# USB_hub_FTDI.net
KiCad netlist of a schematic drawn in EAGLE
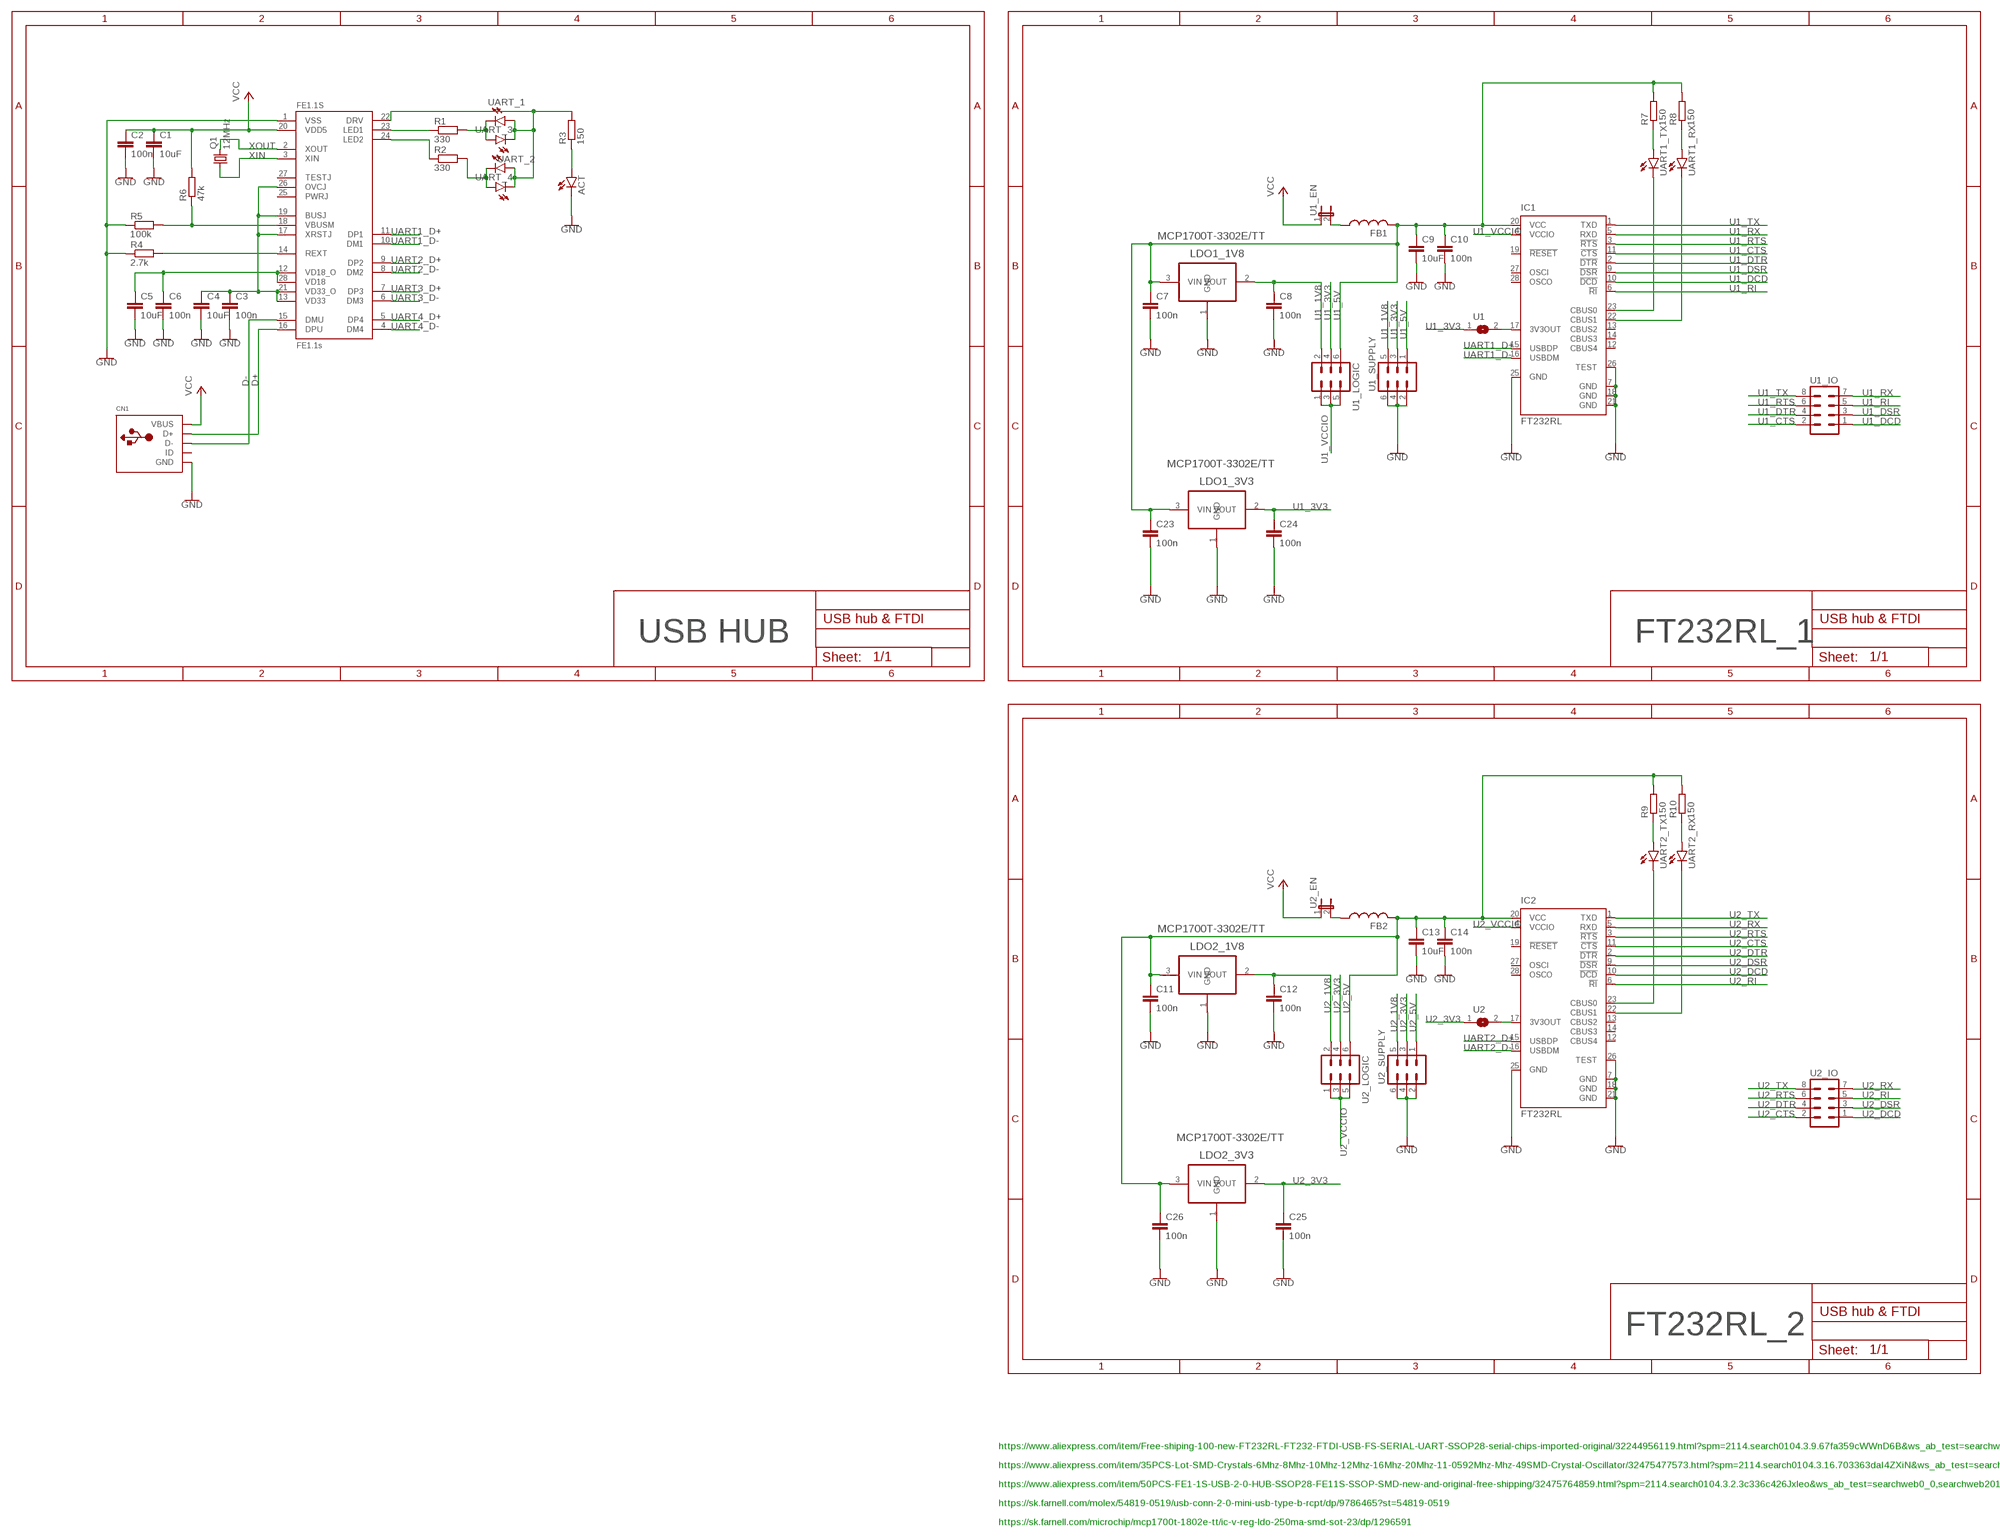
[diagram p0: schematic, sheet 1, part 1 of 2]
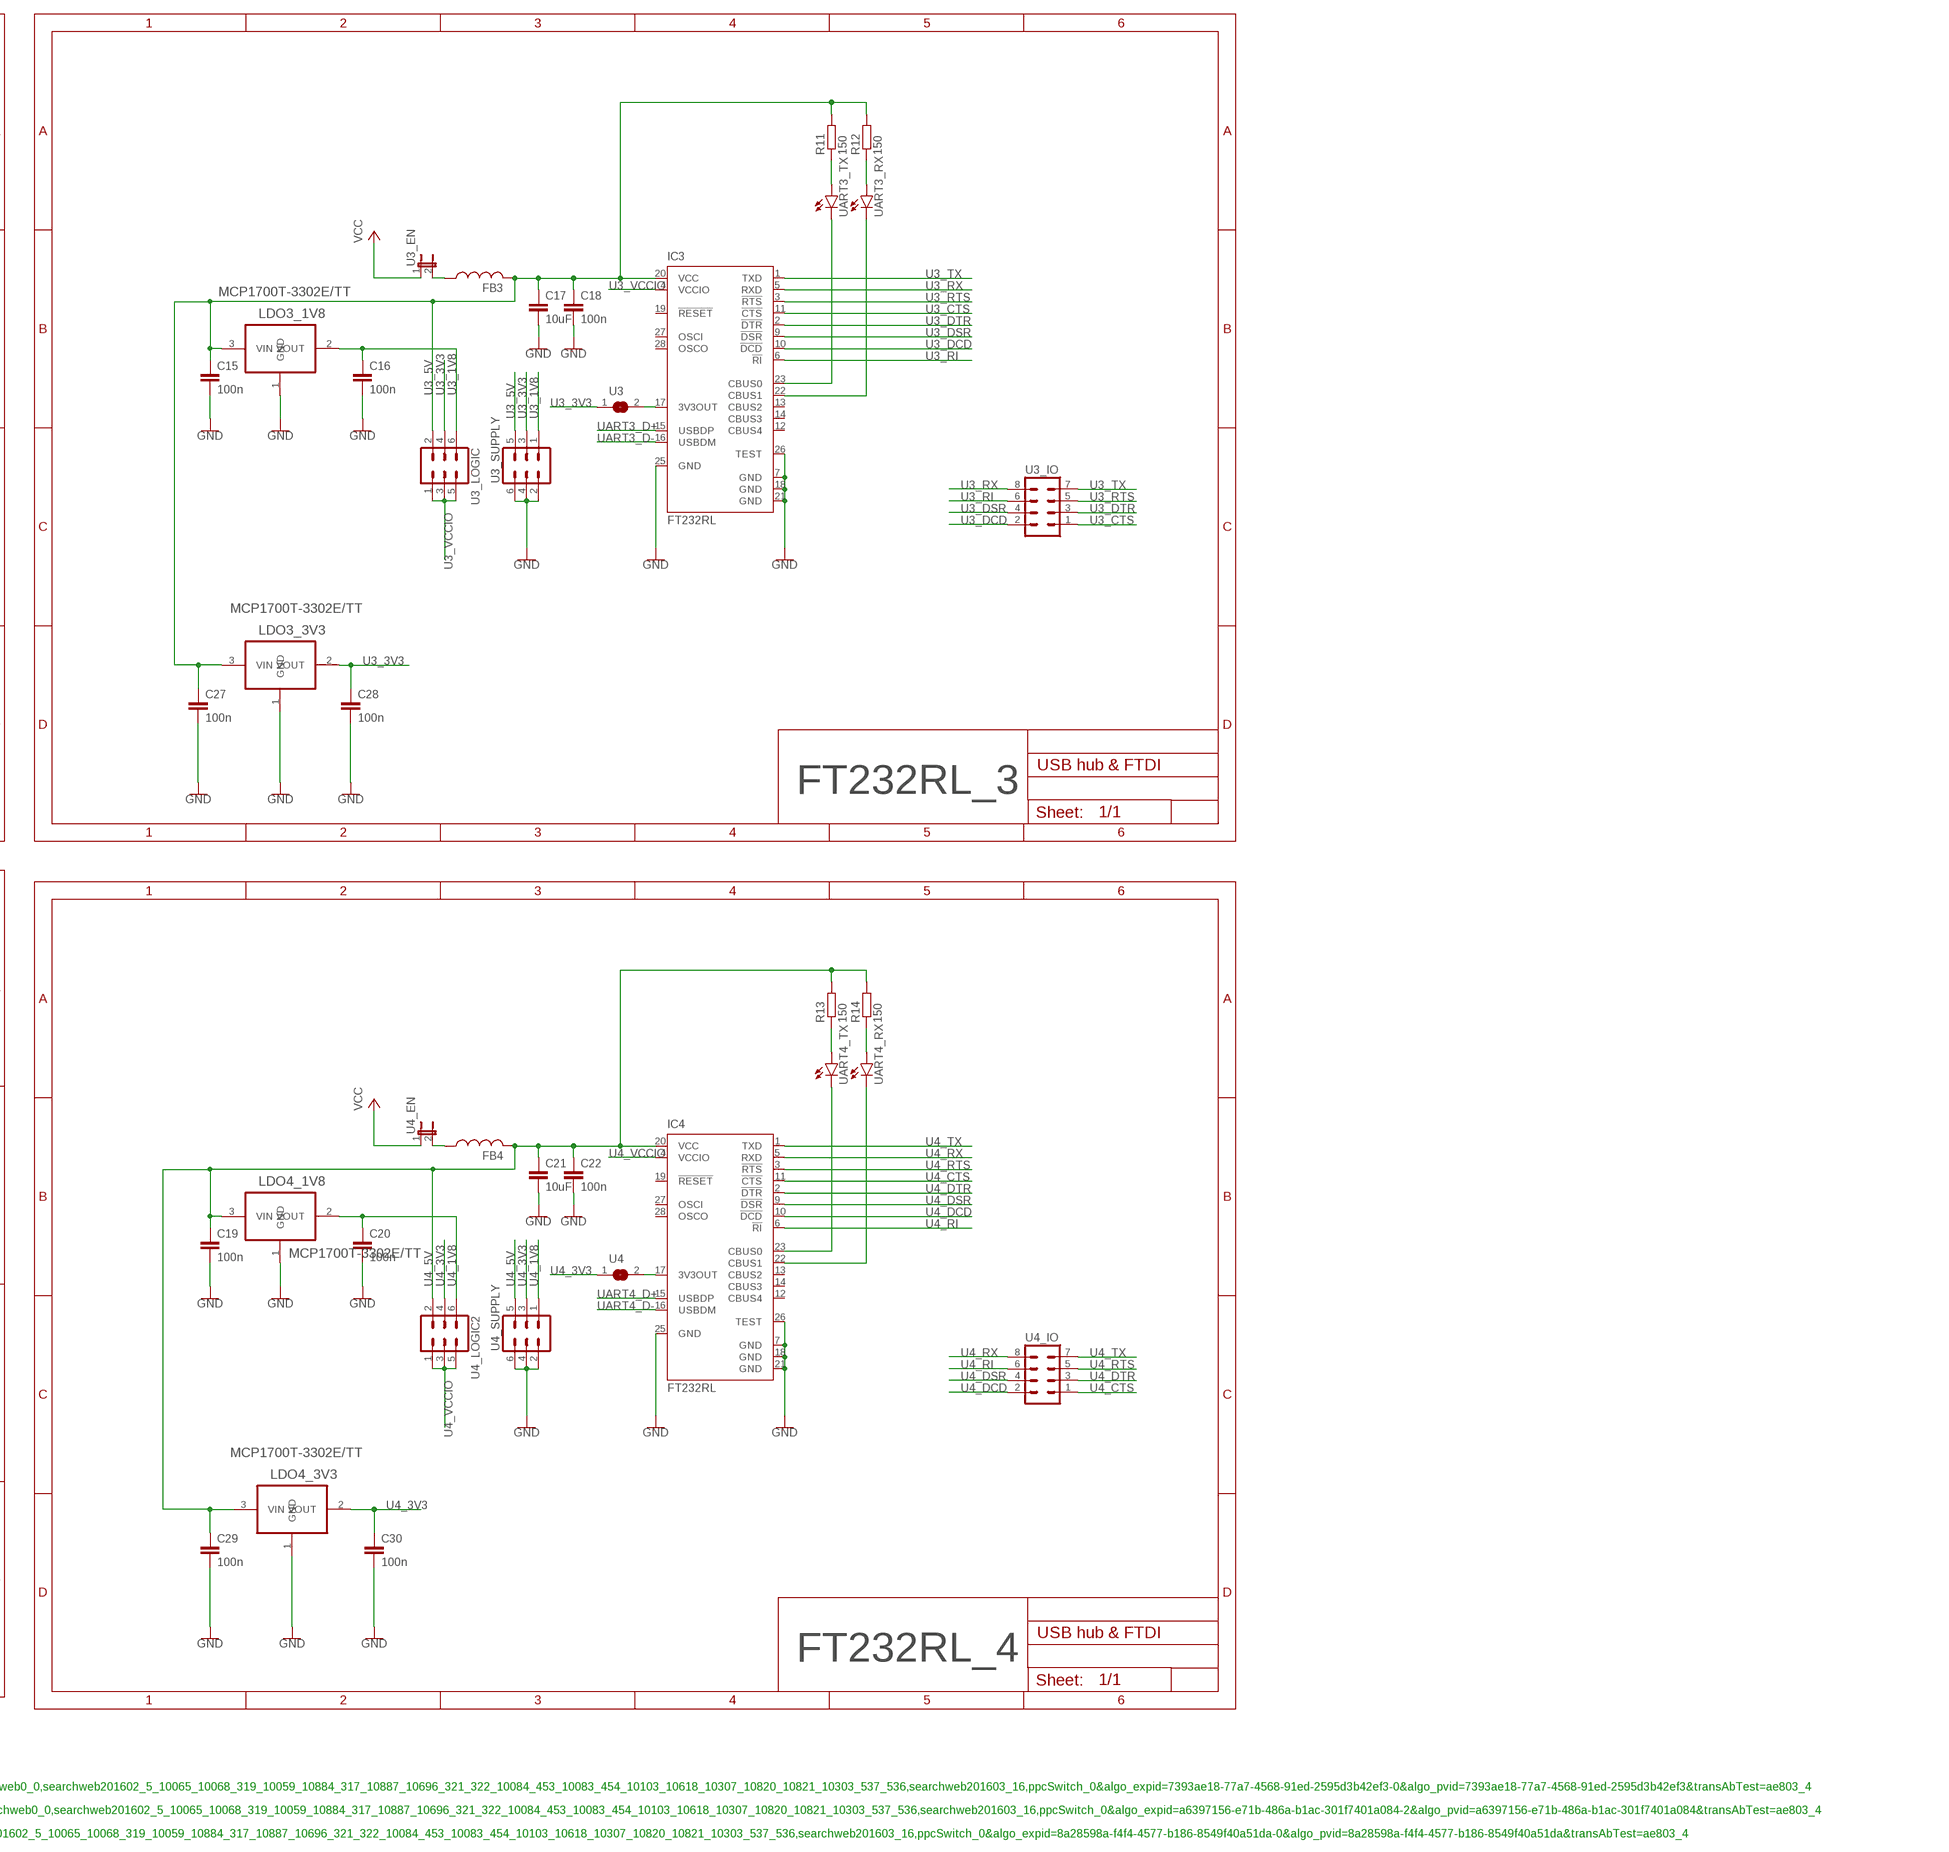
[diagram p1: schematic, sheet 1, part 2 of 2]

(export (version "E")
  (design (tool "Eeschema 10.0.6"))
  (components
    (comp (ref "ACT")
      (value "LEDCHIP-LED0805")
      (footprint "eagle-import:CHIP-LED0805")
      (libsource (lib "eagle-import") (part "LEDCHIP-LED0805"))
    )
    (comp (ref "C1")
      (value "10uF")
      (footprint "eagle-import:C0805")
      (libsource (lib "eagle-import") (part "C-EUC0805"))
    )
    (comp (ref "C2")
      (value "100n")
      (footprint "eagle-import:C0805")
      (libsource (lib "eagle-import") (part "C-EUC0805"))
    )
    (comp (ref "C3")
      (value "100n")
      (footprint "eagle-import:C0805")
      (libsource (lib "eagle-import") (part "C-EUC0805"))
    )
    (comp (ref "C4")
      (value "10uF")
      (footprint "eagle-import:C0805")
      (libsource (lib "eagle-import") (part "C-EUC0805"))
    )
    (comp (ref "C5")
      (value "10uF")
      (footprint "eagle-import:C0805")
      (libsource (lib "eagle-import") (part "C-EUC0805"))
    )
    (comp (ref "C6")
      (value "100n")
      (footprint "eagle-import:C0805")
      (libsource (lib "eagle-import") (part "C-EUC0805"))
    )
    (comp (ref "C7")
      (value "100n")
      (footprint "eagle-import:C0805")
      (libsource (lib "eagle-import") (part "C-EUC0805"))
    )
    (comp (ref "C8")
      (value "100n")
      (footprint "eagle-import:C0805")
      (libsource (lib "eagle-import") (part "C-EUC0805"))
    )
    (comp (ref "C9")
      (value "10uF")
      (footprint "eagle-import:C0805")
      (libsource (lib "eagle-import") (part "C-EUC0805"))
    )
    (comp (ref "C10")
      (value "100n")
      (footprint "eagle-import:C0805")
      (libsource (lib "eagle-import") (part "C-EUC0805"))
    )
    (comp (ref "C11")
      (value "100n")
      (footprint "eagle-import:C0805")
      (libsource (lib "eagle-import") (part "C-EUC0805"))
    )
    (comp (ref "C12")
      (value "100n")
      (footprint "eagle-import:C0805")
      (libsource (lib "eagle-import") (part "C-EUC0805"))
    )
    (comp (ref "C13")
      (value "10uF")
      (footprint "eagle-import:C0805")
      (libsource (lib "eagle-import") (part "C-EUC0805"))
    )
    (comp (ref "C14")
      (value "100n")
      (footprint "eagle-import:C0805")
      (libsource (lib "eagle-import") (part "C-EUC0805"))
    )
    (comp (ref "C15")
      (value "100n")
      (footprint "eagle-import:C0805")
      (libsource (lib "eagle-import") (part "C-EUC0805"))
    )
    (comp (ref "C16")
      (value "100n")
      (footprint "eagle-import:C0805")
      (libsource (lib "eagle-import") (part "C-EUC0805"))
    )
    (comp (ref "C17")
      (value "10uF")
      (footprint "eagle-import:C0805")
      (libsource (lib "eagle-import") (part "C-EUC0805"))
    )
    (comp (ref "C18")
      (value "100n")
      (footprint "eagle-import:C0805")
      (libsource (lib "eagle-import") (part "C-EUC0805"))
    )
    (comp (ref "C19")
      (value "100n")
      (footprint "eagle-import:C0805")
      (libsource (lib "eagle-import") (part "C-EUC0805"))
    )
    (comp (ref "C20")
      (value "100n")
      (footprint "eagle-import:C0805")
      (libsource (lib "eagle-import") (part "C-EUC0805"))
    )
    (comp (ref "C21")
      (value "10uF")
      (footprint "eagle-import:C0805")
      (libsource (lib "eagle-import") (part "C-EUC0805"))
    )
    (comp (ref "C22")
      (value "100n")
      (footprint "eagle-import:C0805")
      (libsource (lib "eagle-import") (part "C-EUC0805"))
    )
    (comp (ref "C23")
      (value "100n")
      (footprint "eagle-import:C0805")
      (libsource (lib "eagle-import") (part "C-EUC0805"))
    )
    (comp (ref "C24")
      (value "100n")
      (footprint "eagle-import:C0805")
      (libsource (lib "eagle-import") (part "C-EUC0805"))
    )
    (comp (ref "C25")
      (value "100n")
      (footprint "eagle-import:C0805")
      (libsource (lib "eagle-import") (part "C-EUC0805"))
    )
    (comp (ref "C26")
      (value "100n")
      (footprint "eagle-import:C0805")
      (libsource (lib "eagle-import") (part "C-EUC0805"))
    )
    (comp (ref "C27")
      (value "100n")
      (footprint "eagle-import:C0805")
      (libsource (lib "eagle-import") (part "C-EUC0805"))
    )
    (comp (ref "C28")
      (value "100n")
      (footprint "eagle-import:C0805")
      (libsource (lib "eagle-import") (part "C-EUC0805"))
    )
    (comp (ref "C29")
      (value "100n")
      (footprint "eagle-import:C0805")
      (libsource (lib "eagle-import") (part "C-EUC0805"))
    )
    (comp (ref "C30")
      (value "100n")
      (footprint "eagle-import:C0805")
      (libsource (lib "eagle-import") (part "C-EUC0805"))
    )
    (comp (ref "CN1")
      (value "USBMOLEX")
      (footprint "eagle-import:USB-MINIB-THM-MOLEX")
      (libsource (lib "eagle-import") (part "USBMOLEX"))
    )
    (comp (ref "FB1")
      (value "FERRITE-BEADB")
      (footprint "eagle-import:0805")
      (libsource (lib "eagle-import") (part "FERRITE-BEADB"))
    )
    (comp (ref "FB2")
      (value "FERRITE-BEADB")
      (footprint "eagle-import:0805")
      (libsource (lib "eagle-import") (part "FERRITE-BEADB"))
    )
    (comp (ref "FB3")
      (value "FERRITE-BEADB")
      (footprint "eagle-import:0805")
      (libsource (lib "eagle-import") (part "FERRITE-BEADB"))
    )
    (comp (ref "FB4")
      (value "FERRITE-BEADB")
      (footprint "eagle-import:0805")
      (libsource (lib "eagle-import") (part "FERRITE-BEADB"))
    )
    (comp (ref "FE1.1S")
      (value "FE1.1S")
      (footprint "eagle-import:FE1.1S_SSOP-28")
      (libsource (lib "eagle-import") (part "FE1.1S"))
    )
    (comp (ref "IC1")
      (value "FT232RL")
      (footprint "eagle-import:SSOP28")
      (libsource (lib "eagle-import") (part "FT232RL"))
    )
    (comp (ref "IC2")
      (value "FT232RL")
      (footprint "eagle-import:SSOP28")
      (libsource (lib "eagle-import") (part "FT232RL"))
    )
    (comp (ref "IC3")
      (value "FT232RL")
      (footprint "eagle-import:SSOP28")
      (libsource (lib "eagle-import") (part "FT232RL"))
    )
    (comp (ref "IC4")
      (value "FT232RL")
      (footprint "eagle-import:SSOP28")
      (libsource (lib "eagle-import") (part "FT232RL"))
    )
    (comp (ref "LDO1_1V8")
      (value "MCP1700T-3302E/TT")
      (footprint "eagle-import:SOT95P237X112-3N")
      (fields (field (name "MF") "Microchip"))
      (libsource (lib "eagle-import") (part "MCP1700T-3302E/TT"))
    )
    (comp (ref "LDO1_3V3")
      (value "MCP1700T-3302E/TT")
      (footprint "eagle-import:SOT95P237X112-3N")
      (fields (field (name "MF") "Microchip"))
      (libsource (lib "eagle-import") (part "MCP1700T-3302E/TT"))
    )
    (comp (ref "LDO2_1V8")
      (value "MCP1700T-3302E/TT")
      (footprint "eagle-import:SOT95P237X112-3N")
      (fields (field (name "MF") "Microchip"))
      (libsource (lib "eagle-import") (part "MCP1700T-3302E/TT"))
    )
    (comp (ref "LDO2_3V3")
      (value "MCP1700T-3302E/TT")
      (footprint "eagle-import:SOT95P237X112-3N")
      (fields (field (name "MF") "Microchip"))
      (libsource (lib "eagle-import") (part "MCP1700T-3302E/TT"))
    )
    (comp (ref "LDO3_1V8")
      (value "MCP1700T-3302E/TT")
      (footprint "eagle-import:SOT95P237X112-3N")
      (fields (field (name "MF") "Microchip"))
      (libsource (lib "eagle-import") (part "MCP1700T-3302E/TT"))
    )
    (comp (ref "LDO3_3V3")
      (value "MCP1700T-3302E/TT")
      (footprint "eagle-import:SOT95P237X112-3N")
      (fields (field (name "MF") "Microchip"))
      (libsource (lib "eagle-import") (part "MCP1700T-3302E/TT"))
    )
    (comp (ref "LDO4_1V8")
      (value "MCP1700T-3302E/TT")
      (footprint "eagle-import:SOT95P237X112-3N")
      (fields (field (name "MF") "Microchip"))
      (libsource (lib "eagle-import") (part "MCP1700T-3302E/TT"))
    )
    (comp (ref "LDO4_3V3")
      (value "MCP1700T-3302E/TT")
      (footprint "eagle-import:SOT95P237X112-3N")
      (fields (field (name "MF") "Microchip"))
      (libsource (lib "eagle-import") (part "MCP1700T-3302E/TT"))
    )
    (comp (ref "Q1")
      (value "12MHz")
      (footprint "eagle-import:HC49UP")
      (libsource (lib "eagle-import") (part "CRYSTALHC49UP"))
    )
    (comp (ref "R1")
      (value "330")
      (footprint "eagle-import:R0805W")
      (libsource (lib "eagle-import") (part "R-EU_R0805W"))
    )
    (comp (ref "R2")
      (value "330")
      (footprint "eagle-import:R0805W")
      (libsource (lib "eagle-import") (part "R-EU_R0805W"))
    )
    (comp (ref "R3")
      (value "150")
      (footprint "eagle-import:R0805W")
      (libsource (lib "eagle-import") (part "R-EU_R0805W"))
    )
    (comp (ref "R4")
      (value "2.7k")
      (footprint "eagle-import:R0805W")
      (libsource (lib "eagle-import") (part "R-EU_R0805W"))
    )
    (comp (ref "R5")
      (value "100k")
      (footprint "eagle-import:R0805W")
      (libsource (lib "eagle-import") (part "R-EU_R0805W"))
    )
    (comp (ref "R6")
      (value "47k")
      (footprint "eagle-import:R0805W")
      (libsource (lib "eagle-import") (part "R-EU_R0805W"))
    )
    (comp (ref "R7")
      (value "150")
      (footprint "eagle-import:R0805W")
      (libsource (lib "eagle-import") (part "R-EU_R0805W"))
    )
    (comp (ref "R8")
      (value "150")
      (footprint "eagle-import:R0805W")
      (libsource (lib "eagle-import") (part "R-EU_R0805W"))
    )
    (comp (ref "R9")
      (value "150")
      (footprint "eagle-import:R0805W")
      (libsource (lib "eagle-import") (part "R-EU_R0805W"))
    )
    (comp (ref "R10")
      (value "150")
      (footprint "eagle-import:R0805W")
      (libsource (lib "eagle-import") (part "R-EU_R0805W"))
    )
    (comp (ref "R11")
      (value "150")
      (footprint "eagle-import:R0805W")
      (libsource (lib "eagle-import") (part "R-EU_R0805W"))
    )
    (comp (ref "R12")
      (value "150")
      (footprint "eagle-import:R0805W")
      (libsource (lib "eagle-import") (part "R-EU_R0805W"))
    )
    (comp (ref "R13")
      (value "150")
      (footprint "eagle-import:R0805W")
      (libsource (lib "eagle-import") (part "R-EU_R0805W"))
    )
    (comp (ref "R14")
      (value "150")
      (footprint "eagle-import:R0805W")
      (libsource (lib "eagle-import") (part "R-EU_R0805W"))
    )
    (comp (ref "U1") (value "SJ") (footprint "eagle-import:SJ") (libsource (lib "eagle-import") (part "SJ")))
    (comp (ref "U1_EN")
      (value "JP1E")
      (footprint "eagle-import:JP1")
      (libsource (lib "eagle-import") (part "JP1E"))
    )
    (comp (ref "U1_IO")
      (value "MA04-2")
      (footprint "eagle-import:MA04-2")
      (libsource (lib "eagle-import") (part "MA04-2"))
    )
    (comp (ref "U1_LOGIC")
      (value "MA03-2")
      (footprint "eagle-import:MA03-2")
      (libsource (lib "eagle-import") (part "MA03-2"))
    )
    (comp (ref "U1_SUPPLY")
      (value "MA03-2")
      (footprint "eagle-import:MA03-2")
      (libsource (lib "eagle-import") (part "MA03-2"))
    )
    (comp (ref "U2") (value "SJ") (footprint "eagle-import:SJ") (libsource (lib "eagle-import") (part "SJ")))
    (comp (ref "U2_EN")
      (value "JP1E")
      (footprint "eagle-import:JP1")
      (libsource (lib "eagle-import") (part "JP1E"))
    )
    (comp (ref "U2_IO")
      (value "MA04-2")
      (footprint "eagle-import:MA04-2")
      (libsource (lib "eagle-import") (part "MA04-2"))
    )
    (comp (ref "U2_LOGIC")
      (value "MA03-2")
      (footprint "eagle-import:MA03-2")
      (libsource (lib "eagle-import") (part "MA03-2"))
    )
    (comp (ref "U2_SUPPLY")
      (value "MA03-2")
      (footprint "eagle-import:MA03-2")
      (libsource (lib "eagle-import") (part "MA03-2"))
    )
    (comp (ref "U3") (value "SJ") (footprint "eagle-import:SJ") (libsource (lib "eagle-import") (part "SJ")))
    (comp (ref "U3_EN")
      (value "JP1E")
      (footprint "eagle-import:JP1")
      (libsource (lib "eagle-import") (part "JP1E"))
    )
    (comp (ref "U3_IO")
      (value "MA04-2")
      (footprint "eagle-import:MA04-2")
      (libsource (lib "eagle-import") (part "MA04-2"))
    )
    (comp (ref "U3_LOGIC")
      (value "MA03-2")
      (footprint "eagle-import:MA03-2")
      (libsource (lib "eagle-import") (part "MA03-2"))
    )
    (comp (ref "U3_SUPPLY")
      (value "MA03-2")
      (footprint "eagle-import:MA03-2")
      (libsource (lib "eagle-import") (part "MA03-2"))
    )
    (comp (ref "U4") (value "SJ") (footprint "eagle-import:SJ") (libsource (lib "eagle-import") (part "SJ")))
    (comp (ref "U4_EN")
      (value "JP1E")
      (footprint "eagle-import:JP1")
      (libsource (lib "eagle-import") (part "JP1E"))
    )
    (comp (ref "U4_IO")
      (value "MA04-2")
      (footprint "eagle-import:MA04-2")
      (libsource (lib "eagle-import") (part "MA04-2"))
    )
    (comp (ref "U4_LOGIC2")
      (value "MA03-2")
      (footprint "eagle-import:MA03-2")
      (libsource (lib "eagle-import") (part "MA03-2"))
    )
    (comp (ref "U4_SUPPLY")
      (value "MA03-2")
      (footprint "eagle-import:MA03-2")
      (libsource (lib "eagle-import") (part "MA03-2"))
    )
    (comp (ref "UART1_RX")
      (value "LEDCHIP-LED0805")
      (footprint "eagle-import:CHIP-LED0805")
      (libsource (lib "eagle-import") (part "LEDCHIP-LED0805"))
    )
    (comp (ref "UART1_TX")
      (value "LEDCHIP-LED0805")
      (footprint "eagle-import:CHIP-LED0805")
      (libsource (lib "eagle-import") (part "LEDCHIP-LED0805"))
    )
    (comp (ref "UART2_RX")
      (value "LEDCHIP-LED0805")
      (footprint "eagle-import:CHIP-LED0805")
      (libsource (lib "eagle-import") (part "LEDCHIP-LED0805"))
    )
    (comp (ref "UART2_TX")
      (value "LEDCHIP-LED0805")
      (footprint "eagle-import:CHIP-LED0805")
      (libsource (lib "eagle-import") (part "LEDCHIP-LED0805"))
    )
    (comp (ref "UART3_RX")
      (value "LEDCHIP-LED0805")
      (footprint "eagle-import:CHIP-LED0805")
      (libsource (lib "eagle-import") (part "LEDCHIP-LED0805"))
    )
    (comp (ref "UART3_TX")
      (value "LEDCHIP-LED0805")
      (footprint "eagle-import:CHIP-LED0805")
      (libsource (lib "eagle-import") (part "LEDCHIP-LED0805"))
    )
    (comp (ref "UART4_RX")
      (value "LEDCHIP-LED0805")
      (footprint "eagle-import:CHIP-LED0805")
      (libsource (lib "eagle-import") (part "LEDCHIP-LED0805"))
    )
    (comp (ref "UART4_TX")
      (value "LEDCHIP-LED0805")
      (footprint "eagle-import:CHIP-LED0805")
      (libsource (lib "eagle-import") (part "LEDCHIP-LED0805"))
    )
    (comp (ref "UART_1")
      (value "LEDCHIP-LED0805")
      (footprint "eagle-import:CHIP-LED0805")
      (libsource (lib "eagle-import") (part "LEDCHIP-LED0805"))
    )
    (comp (ref "UART_2")
      (value "LEDCHIP-LED0805")
      (footprint "eagle-import:CHIP-LED0805")
      (libsource (lib "eagle-import") (part "LEDCHIP-LED0805"))
    )
    (comp (ref "UART_3")
      (value "LEDCHIP-LED0805")
      (footprint "eagle-import:CHIP-LED0805")
      (libsource (lib "eagle-import") (part "LEDCHIP-LED0805"))
    )
    (comp (ref "UART_4")
      (value "LEDCHIP-LED0805")
      (footprint "eagle-import:CHIP-LED0805")
      (libsource (lib "eagle-import") (part "LEDCHIP-LED0805"))
    )
  )
  (nets
    (net (code "1") (name "/D+") (class "Default")
      (node (ref "CN1") (pin "D+") (pinfunction "D+_D+") (pintype "bidirectional"))
      (node (ref "FE1.1S") (pin "16") (pinfunction "DPU_16") (pintype "bidirectional"))
    )
    (net (code "2") (name "/D-") (class "Default")
      (node (ref "CN1") (pin "D-") (pinfunction "D-_D-") (pintype "bidirectional"))
      (node (ref "FE1.1S") (pin "15") (pinfunction "DMU_15") (pintype "bidirectional"))
    )
    (net (code "3") (name "/U1_1V8") (class "Default")
      (node (ref "C8") (pin "1") (pinfunction "1_1") (pintype "passive"))
      (node (ref "LDO1_1V8") (pin "2") (pinfunction "VOUT_2") (pintype "output"))
      (node (ref "U1_LOGIC") (pin "2") (pinfunction "2_2") (pintype "passive"))
      (node (ref "U1_SUPPLY") (pin "5") (pinfunction "5_5") (pintype "passive"))
    )
    (net (code "4") (name "/U1_3V3") (class "Default")
      (node (ref "C24") (pin "1") (pinfunction "1_1") (pintype "passive"))
      (node (ref "LDO1_3V3") (pin "2") (pinfunction "VOUT_2") (pintype "output"))
      (node (ref "U1") (pin "1") (pinfunction "1_1") (pintype "passive"))
      (node (ref "U1_LOGIC") (pin "4") (pinfunction "4_4") (pintype "passive"))
      (node (ref "U1_SUPPLY") (pin "3") (pinfunction "3_3") (pintype "passive"))
    )
    (net (code "5") (name "/U1_5V") (class "Default")
      (node (ref "C10") (pin "1") (pinfunction "1_1") (pintype "passive"))
      (node (ref "C23") (pin "1") (pinfunction "1_1") (pintype "passive"))
      (node (ref "C7") (pin "1") (pinfunction "1_1") (pintype "passive"))
      (node (ref "C9") (pin "1") (pinfunction "1_1") (pintype "passive"))
      (node (ref "FB1") (pin "2") (pinfunction "2_2") (pintype "passive"))
      (node (ref "IC1") (pin "20") (pinfunction "VCC_20") (pintype "power_in"))
      (node (ref "LDO1_1V8") (pin "3") (pinfunction "VIN_3") (pintype "input"))
      (node (ref "LDO1_3V3") (pin "3") (pinfunction "VIN_3") (pintype "input"))
      (node (ref "R7") (pin "2") (pinfunction "2_2") (pintype "passive"))
      (node (ref "R8") (pin "2") (pinfunction "2_2") (pintype "passive"))
      (node (ref "U1_LOGIC") (pin "6") (pinfunction "6_6") (pintype "passive"))
      (node (ref "U1_SUPPLY") (pin "1") (pinfunction "1_1") (pintype "passive"))
    )
    (net (code "6") (name "/U1_CTS") (class "Default")
      (node (ref "IC1") (pin "11") (pinfunction "~{CTS}_11") (pintype "input"))
      (node (ref "U1_IO") (pin "2") (pinfunction "2_2") (pintype "passive"))
    )
    (net (code "7") (name "/U1_DCD") (class "Default")
      (node (ref "IC1") (pin "10") (pinfunction "~{DCD}_10") (pintype "input"))
      (node (ref "U1_IO") (pin "1") (pinfunction "1_1") (pintype "passive"))
    )
    (net (code "8") (name "/U1_DSR") (class "Default")
      (node (ref "IC1") (pin "9") (pinfunction "~{DSR}_9") (pintype "input"))
      (node (ref "U1_IO") (pin "3") (pinfunction "3_3") (pintype "passive"))
    )
    (net (code "9") (name "/U1_DTR") (class "Default")
      (node (ref "IC1") (pin "2") (pinfunction "~{DTR}_2") (pintype "output"))
      (node (ref "U1_IO") (pin "4") (pinfunction "4_4") (pintype "passive"))
    )
    (net (code "10") (name "/U1_RI") (class "Default")
      (node (ref "IC1") (pin "6") (pinfunction "~{RI}_6") (pintype "input"))
      (node (ref "U1_IO") (pin "5") (pinfunction "5_5") (pintype "passive"))
    )
    (net (code "11") (name "/U1_RTS") (class "Default")
      (node (ref "IC1") (pin "3") (pinfunction "~{RTS}_3") (pintype "output"))
      (node (ref "U1_IO") (pin "6") (pinfunction "6_6") (pintype "passive"))
    )
    (net (code "12") (name "/U1_RX") (class "Default")
      (node (ref "IC1") (pin "5") (pinfunction "RXD_5") (pintype "input"))
      (node (ref "U1_IO") (pin "7") (pinfunction "7_7") (pintype "passive"))
    )
    (net (code "13") (name "/U1_TX") (class "Default")
      (node (ref "IC1") (pin "1") (pinfunction "TXD_1") (pintype "output"))
      (node (ref "U1_IO") (pin "8") (pinfunction "8_8") (pintype "passive"))
    )
    (net (code "14") (name "/U1_VCCIO") (class "Default")
      (node (ref "IC1") (pin "4") (pinfunction "VCCIO_4") (pintype "power_in"))
      (node (ref "U1_LOGIC") (pin "1") (pinfunction "1_1") (pintype "passive"))
      (node (ref "U1_LOGIC") (pin "3") (pinfunction "3_3") (pintype "passive"))
      (node (ref "U1_LOGIC") (pin "5") (pinfunction "5_5") (pintype "passive"))
    )
    (net (code "15") (name "/U2_1V8") (class "Default")
      (node (ref "C12") (pin "1") (pinfunction "1_1") (pintype "passive"))
      (node (ref "LDO2_1V8") (pin "2") (pinfunction "VOUT_2") (pintype "output"))
      (node (ref "U2_LOGIC") (pin "2") (pinfunction "2_2") (pintype "passive"))
      (node (ref "U2_SUPPLY") (pin "5") (pinfunction "5_5") (pintype "passive"))
    )
    (net (code "16") (name "/U2_3V3") (class "Default")
      (node (ref "C25") (pin "1") (pinfunction "1_1") (pintype "passive"))
      (node (ref "LDO2_3V3") (pin "2") (pinfunction "VOUT_2") (pintype "output"))
      (node (ref "U2") (pin "1") (pinfunction "1_1") (pintype "passive"))
      (node (ref "U2_LOGIC") (pin "4") (pinfunction "4_4") (pintype "passive"))
      (node (ref "U2_SUPPLY") (pin "3") (pinfunction "3_3") (pintype "passive"))
    )
    (net (code "17") (name "/U2_5V") (class "Default")
      (node (ref "C11") (pin "1") (pinfunction "1_1") (pintype "passive"))
      (node (ref "C13") (pin "1") (pinfunction "1_1") (pintype "passive"))
      (node (ref "C14") (pin "1") (pinfunction "1_1") (pintype "passive"))
      (node (ref "C26") (pin "1") (pinfunction "1_1") (pintype "passive"))
      (node (ref "FB2") (pin "2") (pinfunction "2_2") (pintype "passive"))
      (node (ref "IC2") (pin "20") (pinfunction "VCC_20") (pintype "power_in"))
      (node (ref "LDO2_1V8") (pin "3") (pinfunction "VIN_3") (pintype "input"))
      (node (ref "LDO2_3V3") (pin "3") (pinfunction "VIN_3") (pintype "input"))
      (node (ref "R10") (pin "2") (pinfunction "2_2") (pintype "passive"))
      (node (ref "R9") (pin "2") (pinfunction "2_2") (pintype "passive"))
      (node (ref "U2_LOGIC") (pin "6") (pinfunction "6_6") (pintype "passive"))
      (node (ref "U2_SUPPLY") (pin "1") (pinfunction "1_1") (pintype "passive"))
    )
    (net (code "18") (name "/U2_CTS") (class "Default")
      (node (ref "IC2") (pin "11") (pinfunction "~{CTS}_11") (pintype "input"))
      (node (ref "U2_IO") (pin "2") (pinfunction "2_2") (pintype "passive"))
    )
    (net (code "19") (name "/U2_DCD") (class "Default")
      (node (ref "IC2") (pin "10") (pinfunction "~{DCD}_10") (pintype "input"))
      (node (ref "U2_IO") (pin "1") (pinfunction "1_1") (pintype "passive"))
    )
    (net (code "20") (name "/U2_DSR") (class "Default")
      (node (ref "IC2") (pin "9") (pinfunction "~{DSR}_9") (pintype "input"))
      (node (ref "U2_IO") (pin "3") (pinfunction "3_3") (pintype "passive"))
    )
    (net (code "21") (name "/U2_DTR") (class "Default")
      (node (ref "IC2") (pin "2") (pinfunction "~{DTR}_2") (pintype "output"))
      (node (ref "U2_IO") (pin "4") (pinfunction "4_4") (pintype "passive"))
    )
    (net (code "22") (name "/U2_RI") (class "Default")
      (node (ref "IC2") (pin "6") (pinfunction "~{RI}_6") (pintype "input"))
      (node (ref "U2_IO") (pin "5") (pinfunction "5_5") (pintype "passive"))
    )
    (net (code "23") (name "/U2_RTS") (class "Default")
      (node (ref "IC2") (pin "3") (pinfunction "~{RTS}_3") (pintype "output"))
      (node (ref "U2_IO") (pin "6") (pinfunction "6_6") (pintype "passive"))
    )
    (net (code "24") (name "/U2_RX") (class "Default")
      (node (ref "IC2") (pin "5") (pinfunction "RXD_5") (pintype "input"))
      (node (ref "U2_IO") (pin "7") (pinfunction "7_7") (pintype "passive"))
    )
    (net (code "25") (name "/U2_TX") (class "Default")
      (node (ref "IC2") (pin "1") (pinfunction "TXD_1") (pintype "output"))
      (node (ref "U2_IO") (pin "8") (pinfunction "8_8") (pintype "passive"))
    )
    (net (code "26") (name "/U2_VCCIO") (class "Default")
      (node (ref "IC2") (pin "4") (pinfunction "VCCIO_4") (pintype "power_in"))
      (node (ref "U2_LOGIC") (pin "1") (pinfunction "1_1") (pintype "passive"))
      (node (ref "U2_LOGIC") (pin "3") (pinfunction "3_3") (pintype "passive"))
      (node (ref "U2_LOGIC") (pin "5") (pinfunction "5_5") (pintype "passive"))
    )
    (net (code "27") (name "/U3_1V8") (class "Default")
      (node (ref "C16") (pin "1") (pinfunction "1_1") (pintype "passive"))
      (node (ref "LDO3_1V8") (pin "2") (pinfunction "VOUT_2") (pintype "output"))
      (node (ref "U3_LOGIC") (pin "6") (pinfunction "6_6") (pintype "passive"))
      (node (ref "U3_SUPPLY") (pin "1") (pinfunction "1_1") (pintype "passive"))
    )
    (net (code "28") (name "/U3_3V3") (class "Default")
      (node (ref "C28") (pin "1") (pinfunction "1_1") (pintype "passive"))
      (node (ref "LDO3_3V3") (pin "2") (pinfunction "VOUT_2") (pintype "output"))
      (node (ref "U3") (pin "1") (pinfunction "1_1") (pintype "passive"))
      (node (ref "U3_LOGIC") (pin "4") (pinfunction "4_4") (pintype "passive"))
      (node (ref "U3_SUPPLY") (pin "3") (pinfunction "3_3") (pintype "passive"))
    )
    (net (code "29") (name "/U3_5V") (class "Default")
      (node (ref "C15") (pin "1") (pinfunction "1_1") (pintype "passive"))
      (node (ref "C17") (pin "1") (pinfunction "1_1") (pintype "passive"))
      (node (ref "C18") (pin "1") (pinfunction "1_1") (pintype "passive"))
      (node (ref "C27") (pin "1") (pinfunction "1_1") (pintype "passive"))
      (node (ref "FB3") (pin "2") (pinfunction "2_2") (pintype "passive"))
      (node (ref "IC3") (pin "20") (pinfunction "VCC_20") (pintype "power_in"))
      (node (ref "LDO3_1V8") (pin "3") (pinfunction "VIN_3") (pintype "input"))
      (node (ref "LDO3_3V3") (pin "3") (pinfunction "VIN_3") (pintype "input"))
      (node (ref "R11") (pin "2") (pinfunction "2_2") (pintype "passive"))
      (node (ref "R12") (pin "2") (pinfunction "2_2") (pintype "passive"))
      (node (ref "U3_LOGIC") (pin "2") (pinfunction "2_2") (pintype "passive"))
      (node (ref "U3_SUPPLY") (pin "5") (pinfunction "5_5") (pintype "passive"))
    )
    (net (code "30") (name "/U3_CTS") (class "Default")
      (node (ref "IC3") (pin "11") (pinfunction "~{CTS}_11") (pintype "input"))
      (node (ref "U3_IO") (pin "1") (pinfunction "1_1") (pintype "passive"))
    )
    (net (code "31") (name "/U3_DCD") (class "Default")
      (node (ref "IC3") (pin "10") (pinfunction "~{DCD}_10") (pintype "input"))
      (node (ref "U3_IO") (pin "2") (pinfunction "2_2") (pintype "passive"))
    )
    (net (code "32") (name "/U3_DSR") (class "Default")
      (node (ref "IC3") (pin "9") (pinfunction "~{DSR}_9") (pintype "input"))
      (node (ref "U3_IO") (pin "4") (pinfunction "4_4") (pintype "passive"))
    )
    (net (code "33") (name "/U3_DTR") (class "Default")
      (node (ref "IC3") (pin "2") (pinfunction "~{DTR}_2") (pintype "output"))
      (node (ref "U3_IO") (pin "3") (pinfunction "3_3") (pintype "passive"))
    )
    (net (code "34") (name "/U3_RI") (class "Default")
      (node (ref "IC3") (pin "6") (pinfunction "~{RI}_6") (pintype "input"))
      (node (ref "U3_IO") (pin "6") (pinfunction "6_6") (pintype "passive"))
    )
    (net (code "35") (name "/U3_RTS") (class "Default")
      (node (ref "IC3") (pin "3") (pinfunction "~{RTS}_3") (pintype "output"))
      (node (ref "U3_IO") (pin "5") (pinfunction "5_5") (pintype "passive"))
    )
    (net (code "36") (name "/U3_RX") (class "Default")
      (node (ref "IC3") (pin "5") (pinfunction "RXD_5") (pintype "input"))
      (node (ref "U3_IO") (pin "8") (pinfunction "8_8") (pintype "passive"))
    )
    (net (code "37") (name "/U3_TX") (class "Default")
      (node (ref "IC3") (pin "1") (pinfunction "TXD_1") (pintype "output"))
      (node (ref "U3_IO") (pin "7") (pinfunction "7_7") (pintype "passive"))
    )
    (net (code "38") (name "/U3_VCCIO") (class "Default")
      (node (ref "IC3") (pin "4") (pinfunction "VCCIO_4") (pintype "power_in"))
      (node (ref "U3_LOGIC") (pin "1") (pinfunction "1_1") (pintype "passive"))
      (node (ref "U3_LOGIC") (pin "3") (pinfunction "3_3") (pintype "passive"))
      (node (ref "U3_LOGIC") (pin "5") (pinfunction "5_5") (pintype "passive"))
    )
    (net (code "39") (name "/U4_1V8") (class "Default")
      (node (ref "C20") (pin "1") (pinfunction "1_1") (pintype "passive"))
      (node (ref "LDO4_1V8") (pin "2") (pinfunction "VOUT_2") (pintype "output"))
      (node (ref "U4_LOGIC2") (pin "6") (pinfunction "6_6") (pintype "passive"))
      (node (ref "U4_SUPPLY") (pin "1") (pinfunction "1_1") (pintype "passive"))
    )
    (net (code "40") (name "/U4_3V3") (class "Default")
      (node (ref "C30") (pin "1") (pinfunction "1_1") (pintype "passive"))
      (node (ref "LDO4_3V3") (pin "2") (pinfunction "VOUT_2") (pintype "output"))
      (node (ref "U4") (pin "1") (pinfunction "1_1") (pintype "passive"))
      (node (ref "U4_LOGIC2") (pin "4") (pinfunction "4_4") (pintype "passive"))
      (node (ref "U4_SUPPLY") (pin "3") (pinfunction "3_3") (pintype "passive"))
    )
    (net (code "41") (name "/U4_5V") (class "Default")
      (node (ref "C19") (pin "1") (pinfunction "1_1") (pintype "passive"))
      (node (ref "C21") (pin "1") (pinfunction "1_1") (pintype "passive"))
      (node (ref "C22") (pin "1") (pinfunction "1_1") (pintype "passive"))
      (node (ref "C29") (pin "1") (pinfunction "1_1") (pintype "passive"))
      (node (ref "FB4") (pin "2") (pinfunction "2_2") (pintype "passive"))
      (node (ref "IC4") (pin "20") (pinfunction "VCC_20") (pintype "power_in"))
      (node (ref "LDO4_1V8") (pin "3") (pinfunction "VIN_3") (pintype "input"))
      (node (ref "LDO4_3V3") (pin "3") (pinfunction "VIN_3") (pintype "input"))
      (node (ref "R13") (pin "2") (pinfunction "2_2") (pintype "passive"))
      (node (ref "R14") (pin "2") (pinfunction "2_2") (pintype "passive"))
      (node (ref "U4_LOGIC2") (pin "2") (pinfunction "2_2") (pintype "passive"))
      (node (ref "U4_SUPPLY") (pin "5") (pinfunction "5_5") (pintype "passive"))
    )
    (net (code "42") (name "/U4_CTS") (class "Default")
      (node (ref "IC4") (pin "11") (pinfunction "~{CTS}_11") (pintype "input"))
      (node (ref "U4_IO") (pin "1") (pinfunction "1_1") (pintype "passive"))
    )
    (net (code "43") (name "/U4_DCD") (class "Default")
      (node (ref "IC4") (pin "10") (pinfunction "~{DCD}_10") (pintype "input"))
      (node (ref "U4_IO") (pin "2") (pinfunction "2_2") (pintype "passive"))
    )
    (net (code "44") (name "/U4_DSR") (class "Default")
      (node (ref "IC4") (pin "9") (pinfunction "~{DSR}_9") (pintype "input"))
      (node (ref "U4_IO") (pin "4") (pinfunction "4_4") (pintype "passive"))
    )
    (net (code "45") (name "/U4_DTR") (class "Default")
      (node (ref "IC4") (pin "2") (pinfunction "~{DTR}_2") (pintype "output"))
      (node (ref "U4_IO") (pin "3") (pinfunction "3_3") (pintype "passive"))
    )
    (net (code "46") (name "/U4_RI") (class "Default")
      (node (ref "IC4") (pin "6") (pinfunction "~{RI}_6") (pintype "input"))
      (node (ref "U4_IO") (pin "6") (pinfunction "6_6") (pintype "passive"))
    )
    (net (code "47") (name "/U4_RTS") (class "Default")
      (node (ref "IC4") (pin "3") (pinfunction "~{RTS}_3") (pintype "output"))
      (node (ref "U4_IO") (pin "5") (pinfunction "5_5") (pintype "passive"))
    )
    (net (code "48") (name "/U4_RX") (class "Default")
      (node (ref "IC4") (pin "5") (pinfunction "RXD_5") (pintype "input"))
      (node (ref "U4_IO") (pin "8") (pinfunction "8_8") (pintype "passive"))
    )
    (net (code "49") (name "/U4_TX") (class "Default")
      (node (ref "IC4") (pin "1") (pinfunction "TXD_1") (pintype "output"))
      (node (ref "U4_IO") (pin "7") (pinfunction "7_7") (pintype "passive"))
    )
    (net (code "50") (name "/U4_VCCIO") (class "Default")
      (node (ref "IC4") (pin "4") (pinfunction "VCCIO_4") (pintype "power_in"))
      (node (ref "U4_LOGIC2") (pin "1") (pinfunction "1_1") (pintype "passive"))
      (node (ref "U4_LOGIC2") (pin "3") (pinfunction "3_3") (pintype "passive"))
      (node (ref "U4_LOGIC2") (pin "5") (pinfunction "5_5") (pintype "passive"))
    )
    (net (code "51") (name "/UART1_D+") (class "Default")
      (node (ref "FE1.1S") (pin "11") (pinfunction "DP1_11") (pintype "bidirectional"))
      (node (ref "IC1") (pin "15") (pinfunction "USBDP_15") (pintype "bidirectional"))
    )
    (net (code "52") (name "/UART1_D-") (class "Default")
      (node (ref "FE1.1S") (pin "10") (pinfunction "DM1_10") (pintype "bidirectional"))
      (node (ref "IC1") (pin "16") (pinfunction "USBDM_16") (pintype "bidirectional"))
    )
    (net (code "53") (name "/UART2_D+") (class "Default")
      (node (ref "FE1.1S") (pin "9") (pinfunction "DP2_9") (pintype "bidirectional"))
      (node (ref "IC2") (pin "15") (pinfunction "USBDP_15") (pintype "bidirectional"))
    )
    (net (code "54") (name "/UART2_D-") (class "Default")
      (node (ref "FE1.1S") (pin "8") (pinfunction "DM2_8") (pintype "bidirectional"))
      (node (ref "IC2") (pin "16") (pinfunction "USBDM_16") (pintype "bidirectional"))
    )
    (net (code "55") (name "/UART3_D+") (class "Default")
      (node (ref "FE1.1S") (pin "7") (pinfunction "DP3_7") (pintype "bidirectional"))
      (node (ref "IC3") (pin "15") (pinfunction "USBDP_15") (pintype "bidirectional"))
    )
    (net (code "56") (name "/UART3_D-") (class "Default")
      (node (ref "FE1.1S") (pin "6") (pinfunction "DM3_6") (pintype "bidirectional"))
      (node (ref "IC3") (pin "16") (pinfunction "USBDM_16") (pintype "bidirectional"))
    )
    (net (code "57") (name "/UART4_D+") (class "Default")
      (node (ref "FE1.1S") (pin "5") (pinfunction "DP4_5") (pintype "bidirectional"))
      (node (ref "IC4") (pin "15") (pinfunction "USBDP_15") (pintype "bidirectional"))
    )
    (net (code "58") (name "/UART4_D-") (class "Default")
      (node (ref "FE1.1S") (pin "4") (pinfunction "DM4_4") (pintype "bidirectional"))
      (node (ref "IC4") (pin "16") (pinfunction "USBDM_16") (pintype "bidirectional"))
    )
    (net (code "59") (name "/XIN") (class "Default")
      (node (ref "FE1.1S") (pin "3") (pinfunction "XIN_3") (pintype "bidirectional"))
      (node (ref "Q1") (pin "1") (pinfunction "1_1") (pintype "passive"))
    )
    (net (code "60") (name "/XOUT") (class "Default")
      (node (ref "FE1.1S") (pin "2") (pinfunction "XOUT_2") (pintype "bidirectional"))
      (node (ref "Q1") (pin "2") (pinfunction "2_2") (pintype "passive"))
    )
    (net (code "61") (name "GND") (class "Default")
      (node (ref "ACT") (pin "C") (pinfunction "C_C") (pintype "passive"))
      (node (ref "C1") (pin "2") (pinfunction "2_2") (pintype "passive"))
      (node (ref "C10") (pin "2") (pinfunction "2_2") (pintype "passive"))
      (node (ref "C11") (pin "2") (pinfunction "2_2") (pintype "passive"))
      (node (ref "C12") (pin "2") (pinfunction "2_2") (pintype "passive"))
      (node (ref "C13") (pin "2") (pinfunction "2_2") (pintype "passive"))
      (node (ref "C14") (pin "2") (pinfunction "2_2") (pintype "passive"))
      (node (ref "C15") (pin "2") (pinfunction "2_2") (pintype "passive"))
      (node (ref "C16") (pin "2") (pinfunction "2_2") (pintype "passive"))
      (node (ref "C17") (pin "2") (pinfunction "2_2") (pintype "passive"))
      (node (ref "C18") (pin "2") (pinfunction "2_2") (pintype "passive"))
      (node (ref "C19") (pin "2") (pinfunction "2_2") (pintype "passive"))
      (node (ref "C2") (pin "2") (pinfunction "2_2") (pintype "passive"))
      (node (ref "C20") (pin "2") (pinfunction "2_2") (pintype "passive"))
      (node (ref "C21") (pin "2") (pinfunction "2_2") (pintype "passive"))
      (node (ref "C22") (pin "2") (pinfunction "2_2") (pintype "passive"))
      (node (ref "C23") (pin "2") (pinfunction "2_2") (pintype "passive"))
      (node (ref "C24") (pin "2") (pinfunction "2_2") (pintype "passive"))
      (node (ref "C25") (pin "2") (pinfunction "2_2") (pintype "passive"))
      (node (ref "C26") (pin "2") (pinfunction "2_2") (pintype "passive"))
      (node (ref "C27") (pin "2") (pinfunction "2_2") (pintype "passive"))
      (node (ref "C28") (pin "2") (pinfunction "2_2") (pintype "passive"))
      (node (ref "C29") (pin "2") (pinfunction "2_2") (pintype "passive"))
      (node (ref "C3") (pin "2") (pinfunction "2_2") (pintype "passive"))
      (node (ref "C30") (pin "2") (pinfunction "2_2") (pintype "passive"))
      (node (ref "C4") (pin "2") (pinfunction "2_2") (pintype "passive"))
      (node (ref "C5") (pin "2") (pinfunction "2_2") (pintype "passive"))
      (node (ref "C6") (pin "2") (pinfunction "2_2") (pintype "passive"))
      (node (ref "C7") (pin "2") (pinfunction "2_2") (pintype "passive"))
      (node (ref "C8") (pin "2") (pinfunction "2_2") (pintype "passive"))
      (node (ref "C9") (pin "2") (pinfunction "2_2") (pintype "passive"))
      (node (ref "CN1") (pin "GND") (pinfunction "GND_GND") (pintype "power_in"))
      (node (ref "FE1.1S") (pin "1") (pinfunction "VSS_1") (pintype "bidirectional"))
      (node (ref "IC1") (pin "18") (pinfunction "GND_18") (pintype "power_in"))
      (node (ref "IC1") (pin "21") (pinfunction "GND_21") (pintype "power_in"))
      (node (ref "IC1") (pin "25") (pinfunction "GND_25") (pintype "power_in"))
      (node (ref "IC1") (pin "26") (pinfunction "TEST_26") (pintype "input"))
      (node (ref "IC1") (pin "7") (pinfunction "GND_7") (pintype "power_in"))
      (node (ref "IC2") (pin "18") (pinfunction "GND_18") (pintype "power_in"))
      (node (ref "IC2") (pin "21") (pinfunction "GND_21") (pintype "power_in"))
      (node (ref "IC2") (pin "25") (pinfunction "GND_25") (pintype "power_in"))
      (node (ref "IC2") (pin "26") (pinfunction "TEST_26") (pintype "input"))
      (node (ref "IC2") (pin "7") (pinfunction "GND_7") (pintype "power_in"))
      (node (ref "IC3") (pin "18") (pinfunction "GND_18") (pintype "power_in"))
      (node (ref "IC3") (pin "21") (pinfunction "GND_21") (pintype "power_in"))
      (node (ref "IC3") (pin "25") (pinfunction "GND_25") (pintype "power_in"))
      (node (ref "IC3") (pin "26") (pinfunction "TEST_26") (pintype "input"))
      (node (ref "IC3") (pin "7") (pinfunction "GND_7") (pintype "power_in"))
      (node (ref "IC4") (pin "18") (pinfunction "GND_18") (pintype "power_in"))
      (node (ref "IC4") (pin "21") (pinfunction "GND_21") (pintype "power_in"))
      (node (ref "IC4") (pin "25") (pinfunction "GND_25") (pintype "power_in"))
      (node (ref "IC4") (pin "26") (pinfunction "TEST_26") (pintype "input"))
      (node (ref "IC4") (pin "7") (pinfunction "GND_7") (pintype "power_in"))
      (node (ref "LDO1_1V8") (pin "1") (pinfunction "GND_1") (pintype "passive"))
      (node (ref "LDO1_3V3") (pin "1") (pinfunction "GND_1") (pintype "passive"))
      (node (ref "LDO2_1V8") (pin "1") (pinfunction "GND_1") (pintype "passive"))
      (node (ref "LDO2_3V3") (pin "1") (pinfunction "GND_1") (pintype "passive"))
      (node (ref "LDO3_1V8") (pin "1") (pinfunction "GND_1") (pintype "passive"))
      (node (ref "LDO3_3V3") (pin "1") (pinfunction "GND_1") (pintype "passive"))
      (node (ref "LDO4_1V8") (pin "1") (pinfunction "GND_1") (pintype "passive"))
      (node (ref "LDO4_3V3") (pin "1") (pinfunction "GND_1") (pintype "passive"))
      (node (ref "R4") (pin "1") (pinfunction "1_1") (pintype "passive"))
      (node (ref "R5") (pin "1") (pinfunction "1_1") (pintype "passive"))
      (node (ref "U1_SUPPLY") (pin "2") (pinfunction "2_2") (pintype "passive"))
      (node (ref "U1_SUPPLY") (pin "4") (pinfunction "4_4") (pintype "passive"))
      (node (ref "U1_SUPPLY") (pin "6") (pinfunction "6_6") (pintype "passive"))
      (node (ref "U2_SUPPLY") (pin "2") (pinfunction "2_2") (pintype "passive"))
      (node (ref "U2_SUPPLY") (pin "4") (pinfunction "4_4") (pintype "passive"))
      (node (ref "U2_SUPPLY") (pin "6") (pinfunction "6_6") (pintype "passive"))
      (node (ref "U3_SUPPLY") (pin "2") (pinfunction "2_2") (pintype "passive"))
      (node (ref "U3_SUPPLY") (pin "4") (pinfunction "4_4") (pintype "passive"))
      (node (ref "U3_SUPPLY") (pin "6") (pinfunction "6_6") (pintype "passive"))
      (node (ref "U4_SUPPLY") (pin "2") (pinfunction "2_2") (pintype "passive"))
      (node (ref "U4_SUPPLY") (pin "4") (pinfunction "4_4") (pintype "passive"))
      (node (ref "U4_SUPPLY") (pin "6") (pinfunction "6_6") (pintype "passive"))
    )
    (net (code "62") (name "Net-(ACT-PadA)") (class "Default")
      (node (ref "ACT") (pin "A") (pinfunction "A_A") (pintype "passive"))
      (node (ref "R3") (pin "1") (pinfunction "1_1") (pintype "passive"))
    )
    (net (code "63") (name "Net-(FB1-Pad1)") (class "Default")
      (node (ref "FB1") (pin "1") (pinfunction "1_1") (pintype "passive"))
      (node (ref "U1_EN") (pin "2") (pinfunction "2_2") (pintype "passive"))
    )
    (net (code "64") (name "Net-(FB2-Pad1)") (class "Default")
      (node (ref "FB2") (pin "1") (pinfunction "1_1") (pintype "passive"))
      (node (ref "U2_EN") (pin "2") (pinfunction "2_2") (pintype "passive"))
    )
    (net (code "65") (name "Net-(FB3-Pad1)") (class "Default")
      (node (ref "FB3") (pin "1") (pinfunction "1_1") (pintype "passive"))
      (node (ref "U3_EN") (pin "2") (pinfunction "2_2") (pintype "passive"))
    )
    (net (code "66") (name "Net-(FB4-Pad1)") (class "Default")
      (node (ref "FB4") (pin "1") (pinfunction "1_1") (pintype "passive"))
      (node (ref "U4_EN") (pin "2") (pinfunction "2_2") (pintype "passive"))
    )
    (net (code "67") (name "Net-(FE1.1S-BUSJ)") (class "Default")
      (node (ref "C3") (pin "1") (pinfunction "1_1") (pintype "passive"))
      (node (ref "C4") (pin "1") (pinfunction "1_1") (pintype "passive"))
      (node (ref "FE1.1S") (pin "13") (pinfunction "VD33_13") (pintype "bidirectional"))
      (node (ref "FE1.1S") (pin "17") (pinfunction "XRSTJ_17") (pintype "bidirectional"))
      (node (ref "FE1.1S") (pin "19") (pinfunction "BUSJ_19") (pintype "bidirectional"))
      (node (ref "FE1.1S") (pin "21") (pinfunction "VD33_O_21") (pintype "bidirectional"))
      (node (ref "FE1.1S") (pin "26") (pinfunction "OVCJ_26") (pintype "bidirectional"))
    )
    (net (code "68") (name "Net-(FE1.1S-DRV)") (class "Default")
      (node (ref "FE1.1S") (pin "22") (pinfunction "DRV_22") (pintype "bidirectional"))
      (node (ref "R3") (pin "2") (pinfunction "2_2") (pintype "passive"))
      (node (ref "UART_1") (pin "A") (pinfunction "A_A") (pintype "passive"))
      (node (ref "UART_2") (pin "A") (pinfunction "A_A") (pintype "passive"))
      (node (ref "UART_3") (pin "C") (pinfunction "C_C") (pintype "passive"))
      (node (ref "UART_4") (pin "C") (pinfunction "C_C") (pintype "passive"))
    )
    (net (code "69") (name "Net-(FE1.1S-LED1)") (class "Default")
      (node (ref "FE1.1S") (pin "23") (pinfunction "LED1_23") (pintype "bidirectional"))
      (node (ref "R1") (pin "1") (pinfunction "1_1") (pintype "passive"))
    )
    (net (code "70") (name "Net-(FE1.1S-LED2)") (class "Default")
      (node (ref "FE1.1S") (pin "24") (pinfunction "LED2_24") (pintype "bidirectional"))
      (node (ref "R2") (pin "1") (pinfunction "1_1") (pintype "passive"))
    )
    (net (code "71") (name "Net-(FE1.1S-REXT)") (class "Default")
      (node (ref "FE1.1S") (pin "14") (pinfunction "REXT_14") (pintype "bidirectional"))
      (node (ref "R4") (pin "2") (pinfunction "2_2") (pintype "passive"))
    )
    (net (code "72") (name "Net-(FE1.1S-VBUSM)") (class "Default")
      (node (ref "FE1.1S") (pin "18") (pinfunction "VBUSM_18") (pintype "bidirectional"))
      (node (ref "R5") (pin "2") (pinfunction "2_2") (pintype "passive"))
      (node (ref "R6") (pin "1") (pinfunction "1_1") (pintype "passive"))
    )
    (net (code "73") (name "Net-(FE1.1S-VD18)") (class "Default")
      (node (ref "C5") (pin "1") (pinfunction "1_1") (pintype "passive"))
      (node (ref "C6") (pin "1") (pinfunction "1_1") (pintype "passive"))
      (node (ref "FE1.1S") (pin "12") (pinfunction "VD18_O_12") (pintype "bidirectional"))
      (node (ref "FE1.1S") (pin "28") (pinfunction "VD18_28") (pintype "bidirectional"))
    )
    (net (code "74") (name "Net-(IC1-3V3OUT)") (class "Default")
      (node (ref "IC1") (pin "17") (pinfunction "3V3OUT_17") (pintype "output"))
      (node (ref "U1") (pin "2") (pinfunction "2_2") (pintype "passive"))
    )
    (net (code "75") (name "Net-(IC1-CBUS0)") (class "Default")
      (node (ref "IC1") (pin "23") (pinfunction "CBUS0_23") (pintype "bidirectional"))
      (node (ref "UART1_TX") (pin "C") (pinfunction "C_C") (pintype "passive"))
    )
    (net (code "76") (name "Net-(IC1-CBUS1)") (class "Default")
      (node (ref "IC1") (pin "22") (pinfunction "CBUS1_22") (pintype "bidirectional"))
      (node (ref "UART1_RX") (pin "C") (pinfunction "C_C") (pintype "passive"))
    )
    (net (code "77") (name "Net-(IC2-3V3OUT)") (class "Default")
      (node (ref "IC2") (pin "17") (pinfunction "3V3OUT_17") (pintype "output"))
      (node (ref "U2") (pin "2") (pinfunction "2_2") (pintype "passive"))
    )
    (net (code "78") (name "Net-(IC2-CBUS0)") (class "Default")
      (node (ref "IC2") (pin "23") (pinfunction "CBUS0_23") (pintype "bidirectional"))
      (node (ref "UART2_TX") (pin "C") (pinfunction "C_C") (pintype "passive"))
    )
    (net (code "79") (name "Net-(IC2-CBUS1)") (class "Default")
      (node (ref "IC2") (pin "22") (pinfunction "CBUS1_22") (pintype "bidirectional"))
      (node (ref "UART2_RX") (pin "C") (pinfunction "C_C") (pintype "passive"))
    )
    (net (code "80") (name "Net-(IC3-3V3OUT)") (class "Default")
      (node (ref "IC3") (pin "17") (pinfunction "3V3OUT_17") (pintype "output"))
      (node (ref "U3") (pin "2") (pinfunction "2_2") (pintype "passive"))
    )
    (net (code "81") (name "Net-(IC3-CBUS0)") (class "Default")
      (node (ref "IC3") (pin "23") (pinfunction "CBUS0_23") (pintype "bidirectional"))
      (node (ref "UART3_TX") (pin "C") (pinfunction "C_C") (pintype "passive"))
    )
    (net (code "82") (name "Net-(IC3-CBUS1)") (class "Default")
      (node (ref "IC3") (pin "22") (pinfunction "CBUS1_22") (pintype "bidirectional"))
      (node (ref "UART3_RX") (pin "C") (pinfunction "C_C") (pintype "passive"))
    )
    (net (code "83") (name "Net-(IC4-3V3OUT)") (class "Default")
      (node (ref "IC4") (pin "17") (pinfunction "3V3OUT_17") (pintype "output"))
      (node (ref "U4") (pin "2") (pinfunction "2_2") (pintype "passive"))
    )
    (net (code "84") (name "Net-(IC4-CBUS0)") (class "Default")
      (node (ref "IC4") (pin "23") (pinfunction "CBUS0_23") (pintype "bidirectional"))
      (node (ref "UART4_TX") (pin "C") (pinfunction "C_C") (pintype "passive"))
    )
    (net (code "85") (name "Net-(IC4-CBUS1)") (class "Default")
      (node (ref "IC4") (pin "22") (pinfunction "CBUS1_22") (pintype "bidirectional"))
      (node (ref "UART4_RX") (pin "C") (pinfunction "C_C") (pintype "passive"))
    )
    (net (code "86") (name "Net-(R1-Pad2)") (class "Default")
      (node (ref "R1") (pin "2") (pinfunction "2_2") (pintype "passive"))
      (node (ref "UART_1") (pin "C") (pinfunction "C_C") (pintype "passive"))
      (node (ref "UART_3") (pin "A") (pinfunction "A_A") (pintype "passive"))
    )
    (net (code "87") (name "Net-(R2-Pad2)") (class "Default")
      (node (ref "R2") (pin "2") (pinfunction "2_2") (pintype "passive"))
      (node (ref "UART_2") (pin "C") (pinfunction "C_C") (pintype "passive"))
      (node (ref "UART_4") (pin "A") (pinfunction "A_A") (pintype "passive"))
    )
    (net (code "88") (name "Net-(R7-Pad1)") (class "Default")
      (node (ref "R7") (pin "1") (pinfunction "1_1") (pintype "passive"))
      (node (ref "UART1_TX") (pin "A") (pinfunction "A_A") (pintype "passive"))
    )
    (net (code "89") (name "Net-(R8-Pad1)") (class "Default")
      (node (ref "R8") (pin "1") (pinfunction "1_1") (pintype "passive"))
      (node (ref "UART1_RX") (pin "A") (pinfunction "A_A") (pintype "passive"))
    )
    (net (code "90") (name "Net-(R9-Pad1)") (class "Default")
      (node (ref "R9") (pin "1") (pinfunction "1_1") (pintype "passive"))
      (node (ref "UART2_TX") (pin "A") (pinfunction "A_A") (pintype "passive"))
    )
    (net (code "91") (name "Net-(R10-Pad1)") (class "Default")
      (node (ref "R10") (pin "1") (pinfunction "1_1") (pintype "passive"))
      (node (ref "UART2_RX") (pin "A") (pinfunction "A_A") (pintype "passive"))
    )
    (net (code "92") (name "Net-(R11-Pad1)") (class "Default")
      (node (ref "R11") (pin "1") (pinfunction "1_1") (pintype "passive"))
      (node (ref "UART3_TX") (pin "A") (pinfunction "A_A") (pintype "passive"))
    )
    (net (code "93") (name "Net-(R12-Pad1)") (class "Default")
      (node (ref "R12") (pin "1") (pinfunction "1_1") (pintype "passive"))
      (node (ref "UART3_RX") (pin "A") (pinfunction "A_A") (pintype "passive"))
    )
    (net (code "94") (name "Net-(R13-Pad1)") (class "Default")
      (node (ref "R13") (pin "1") (pinfunction "1_1") (pintype "passive"))
      (node (ref "UART4_TX") (pin "A") (pinfunction "A_A") (pintype "passive"))
    )
    (net (code "95") (name "Net-(R14-Pad1)") (class "Default")
      (node (ref "R14") (pin "1") (pinfunction "1_1") (pintype "passive"))
      (node (ref "UART4_RX") (pin "A") (pinfunction "A_A") (pintype "passive"))
    )
    (net (code "96") (name "VCC") (class "Default")
      (node (ref "C1") (pin "1") (pinfunction "1_1") (pintype "passive"))
      (node (ref "C2") (pin "1") (pinfunction "1_1") (pintype "passive"))
      (node (ref "CN1") (pin "VBUS") (pinfunction "VBUS_VBUS") (pintype "power_in"))
      (node (ref "FE1.1S") (pin "20") (pinfunction "VDD5_20") (pintype "bidirectional"))
      (node (ref "R6") (pin "2") (pinfunction "2_2") (pintype "passive"))
      (node (ref "U1_EN") (pin "1") (pinfunction "1_1") (pintype "passive"))
      (node (ref "U2_EN") (pin "1") (pinfunction "1_1") (pintype "passive"))
      (node (ref "U3_EN") (pin "1") (pinfunction "1_1") (pintype "passive"))
      (node (ref "U4_EN") (pin "1") (pinfunction "1_1") (pintype "passive"))
    )
    (net (code "97") (name "unconnected-(CN1-PadID)") (class "Default")
      (node (ref "CN1") (pin "ID") (pinfunction "ID_ID") (pintype "bidirectional"))
    )
    (net (code "98") (name "unconnected-(FE1.1S-PWRJ-Pad25)") (class "Default")
      (node (ref "FE1.1S") (pin "25") (pinfunction "PWRJ_25") (pintype "bidirectional"))
    )
    (net (code "99") (name "unconnected-(FE1.1S-TESTJ-Pad27)") (class "Default")
      (node (ref "FE1.1S") (pin "27") (pinfunction "TESTJ_27") (pintype "bidirectional"))
    )
    (net (code "100") (name "unconnected-(IC1-CBUS2-Pad13)") (class "Default")
      (node (ref "IC1") (pin "13") (pinfunction "CBUS2_13") (pintype "bidirectional"))
    )
    (net (code "101") (name "unconnected-(IC1-CBUS3-Pad14)") (class "Default")
      (node (ref "IC1") (pin "14") (pinfunction "CBUS3_14") (pintype "bidirectional"))
    )
    (net (code "102") (name "unconnected-(IC1-CBUS4-Pad12)") (class "Default")
      (node (ref "IC1") (pin "12") (pinfunction "CBUS4_12") (pintype "bidirectional"))
    )
    (net (code "103") (name "unconnected-(IC1-OSCI-Pad27)") (class "Default")
      (node (ref "IC1") (pin "27") (pinfunction "OSCI_27") (pintype "input"))
    )
    (net (code "104") (name "unconnected-(IC1-OSCO-Pad28)") (class "Default")
      (node (ref "IC1") (pin "28") (pinfunction "OSCO_28") (pintype "output"))
    )
    (net (code "105") (name "unconnected-(IC1-~{RESET}-Pad19)") (class "Default")
      (node (ref "IC1") (pin "19") (pinfunction "~{RESET}_19") (pintype "input"))
    )
    (net (code "106") (name "unconnected-(IC2-CBUS2-Pad13)") (class "Default")
      (node (ref "IC2") (pin "13") (pinfunction "CBUS2_13") (pintype "bidirectional"))
    )
    (net (code "107") (name "unconnected-(IC2-CBUS3-Pad14)") (class "Default")
      (node (ref "IC2") (pin "14") (pinfunction "CBUS3_14") (pintype "bidirectional"))
    )
    (net (code "108") (name "unconnected-(IC2-CBUS4-Pad12)") (class "Default")
      (node (ref "IC2") (pin "12") (pinfunction "CBUS4_12") (pintype "bidirectional"))
    )
    (net (code "109") (name "unconnected-(IC2-OSCI-Pad27)") (class "Default")
      (node (ref "IC2") (pin "27") (pinfunction "OSCI_27") (pintype "input"))
    )
    (net (code "110") (name "unconnected-(IC2-OSCO-Pad28)") (class "Default")
      (node (ref "IC2") (pin "28") (pinfunction "OSCO_28") (pintype "output"))
    )
    (net (code "111") (name "unconnected-(IC2-~{RESET}-Pad19)") (class "Default")
      (node (ref "IC2") (pin "19") (pinfunction "~{RESET}_19") (pintype "input"))
    )
    (net (code "112") (name "unconnected-(IC3-CBUS2-Pad13)") (class "Default")
      (node (ref "IC3") (pin "13") (pinfunction "CBUS2_13") (pintype "bidirectional"))
    )
    (net (code "113") (name "unconnected-(IC3-CBUS3-Pad14)") (class "Default")
      (node (ref "IC3") (pin "14") (pinfunction "CBUS3_14") (pintype "bidirectional"))
    )
    (net (code "114") (name "unconnected-(IC3-CBUS4-Pad12)") (class "Default")
      (node (ref "IC3") (pin "12") (pinfunction "CBUS4_12") (pintype "bidirectional"))
    )
    (net (code "115") (name "unconnected-(IC3-OSCI-Pad27)") (class "Default")
      (node (ref "IC3") (pin "27") (pinfunction "OSCI_27") (pintype "input"))
    )
    (net (code "116") (name "unconnected-(IC3-OSCO-Pad28)") (class "Default")
      (node (ref "IC3") (pin "28") (pinfunction "OSCO_28") (pintype "output"))
    )
    (net (code "117") (name "unconnected-(IC3-~{RESET}-Pad19)") (class "Default")
      (node (ref "IC3") (pin "19") (pinfunction "~{RESET}_19") (pintype "input"))
    )
    (net (code "118") (name "unconnected-(IC4-CBUS2-Pad13)") (class "Default")
      (node (ref "IC4") (pin "13") (pinfunction "CBUS2_13") (pintype "bidirectional"))
    )
    (net (code "119") (name "unconnected-(IC4-CBUS3-Pad14)") (class "Default")
      (node (ref "IC4") (pin "14") (pinfunction "CBUS3_14") (pintype "bidirectional"))
    )
    (net (code "120") (name "unconnected-(IC4-CBUS4-Pad12)") (class "Default")
      (node (ref "IC4") (pin "12") (pinfunction "CBUS4_12") (pintype "bidirectional"))
    )
    (net (code "121") (name "unconnected-(IC4-OSCI-Pad27)") (class "Default")
      (node (ref "IC4") (pin "27") (pinfunction "OSCI_27") (pintype "input"))
    )
    (net (code "122") (name "unconnected-(IC4-OSCO-Pad28)") (class "Default")
      (node (ref "IC4") (pin "28") (pinfunction "OSCO_28") (pintype "output"))
    )
    (net (code "123") (name "unconnected-(IC4-~{RESET}-Pad19)") (class "Default")
      (node (ref "IC4") (pin "19") (pinfunction "~{RESET}_19") (pintype "input"))
    )
  )
)
